# RTU_LMG_Linear_Voltage_Regulator_3V8.net
KiCad netlist of a schematic drawn in Altium Designer
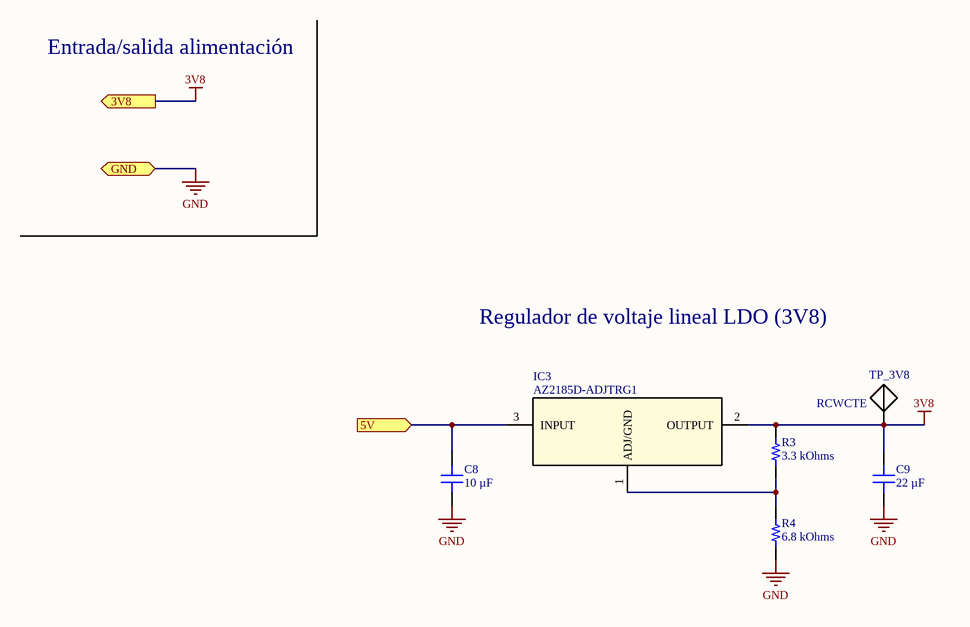
[diagram p0: RTU_LMG_Linear_Voltage_Regulator_3V8.SchDoc]

(export (version "E")
  (design (tool "Eeschema 10.0.6"))
  (components
    (comp (ref "C8")
      (value "10 µF")
      (footprint "PCB - CAPACITOR - MLCC - CAP 1210_3225 - 1MM:CAP 1210_3225 - 1MM")
      (description "CAP CER 10UF 75V X7R 1210")
      (fields
        (field (name "PART NUMBER") "C3225X7R1N106K250AC")
        (field (name "MANUFACTURER") "TDK Corporation")
      )
      (libsource (lib "Celestial Altium Library - altium_library") (part "Capacitor"))
    )
    (comp (ref "C9")
      (value "22 µF")
      (footprint "PCB - CAPACITOR - MLCC - CAP 0805_2012:CAP 0805_2012")
      (description "CAP CER 22UF 16V X5R 0805")
      (fields
        (field (name "PART NUMBER") "CL21A226MOCLRNC")
        (field (name "MANUFACTURER") "Samsung Electro-Mechanics")
      )
      (libsource (lib "Celestial Altium Library - altium_library") (part "Capacitor"))
    )
    (comp (ref "IC3")
      (value "AZ2185D-ADJTRG1")
      (footprint "TO252-3")
      (description "Fuente regulada LDO - 3V8 - 3A")
      (fields (field (name "MOUSER PART NUMBER") "621-AZ2185D-ADJTRG1"))
      (libsource (lib "DIN_DC_Base_Board_components") (part "AZ2185D-ADJTRG1"))
    )
    (comp (ref "R3")
      (value "3.3 kOhms")
      (footprint "RES 0603_1608")
      (description "CRGH0603 1% 3K3 0.2W")
      (fields
        (field (name "PART NUMBER") "CRGH0603F3K3")
        (field (name "MANUFACTURER") "TE Connectivity Passive Product")
      )
      (libsource (lib "Celestial Altium Library - altium_library") (part "Resistor"))
    )
    (comp (ref "R4")
      (value "6.8 kOhms")
      (footprint "RES 0603_1608")
      (description "RES 6.8K OHM 1% 1/4W 0603")
      (fields
        (field (name "PART NUMBER") "CRGP0603F6K8")
        (field (name "MANUFACTURER") "TE Connectivity Passive Product")
      )
      (libsource (lib "Celestial Altium Library - altium_library") (part "Resistor"))
    )
    (comp (ref "TP_3V8")
      (value "RCWCTE")
      (footprint "RCWCTE")
      (description "- PC Test Point - - Plating Surface Mount Mounting Type")
      (fields (field (name "MF") "KOA Speer") (field (name "DIGI-KEY_PART_NUMBER") "2019-RCWCTETR-ND"))
      (libsource (lib "DIN_DC_Base_Board_components") (part "RCWCTE"))
    )
  )
  (nets
    (net (code "1") (name "/5V") (class "Default")
      (node (ref "C8") (pin "1") (pinfunction "1_1") (pintype "passive"))
      (node (ref "IC3") (pin "3") (pinfunction "INPUT_3") (pintype "passive"))
    )
    (net (code "2") (name "3V8") (class "Default")
      (node (ref "C9") (pin "2") (pinfunction "2_2") (pintype "passive"))
      (node (ref "IC3") (pin "2") (pinfunction "OUTPUT_2") (pintype "passive"))
      (node (ref "R3") (pin "2") (pinfunction "2_2") (pintype "passive"))
      (node (ref "TP_3V8") (pin "1") (pinfunction "TP_1") (pintype "passive"))
    )
    (net (code "3") (name "GND") (class "Default")
      (node (ref "C8") (pin "2") (pinfunction "2_2") (pintype "passive"))
      (node (ref "C9") (pin "1") (pinfunction "1_1") (pintype "passive"))
      (node (ref "R4") (pin "1") (pinfunction "1_1") (pintype "passive"))
    )
    (net (code "4") (name "Net-(IC3-ADJ{slash}GND)") (class "Default")
      (node (ref "IC3") (pin "1") (pinfunction "ADJ/GND_1") (pintype "passive"))
      (node (ref "R3") (pin "1") (pinfunction "1_1") (pintype "passive"))
      (node (ref "R4") (pin "2") (pinfunction "2_2") (pintype "passive"))
    )
  )
)
